# SW6106_A_A_B_C_Lighting_MCU_LED.net
KiCad netlist of a schematic drawn in Altium Designer
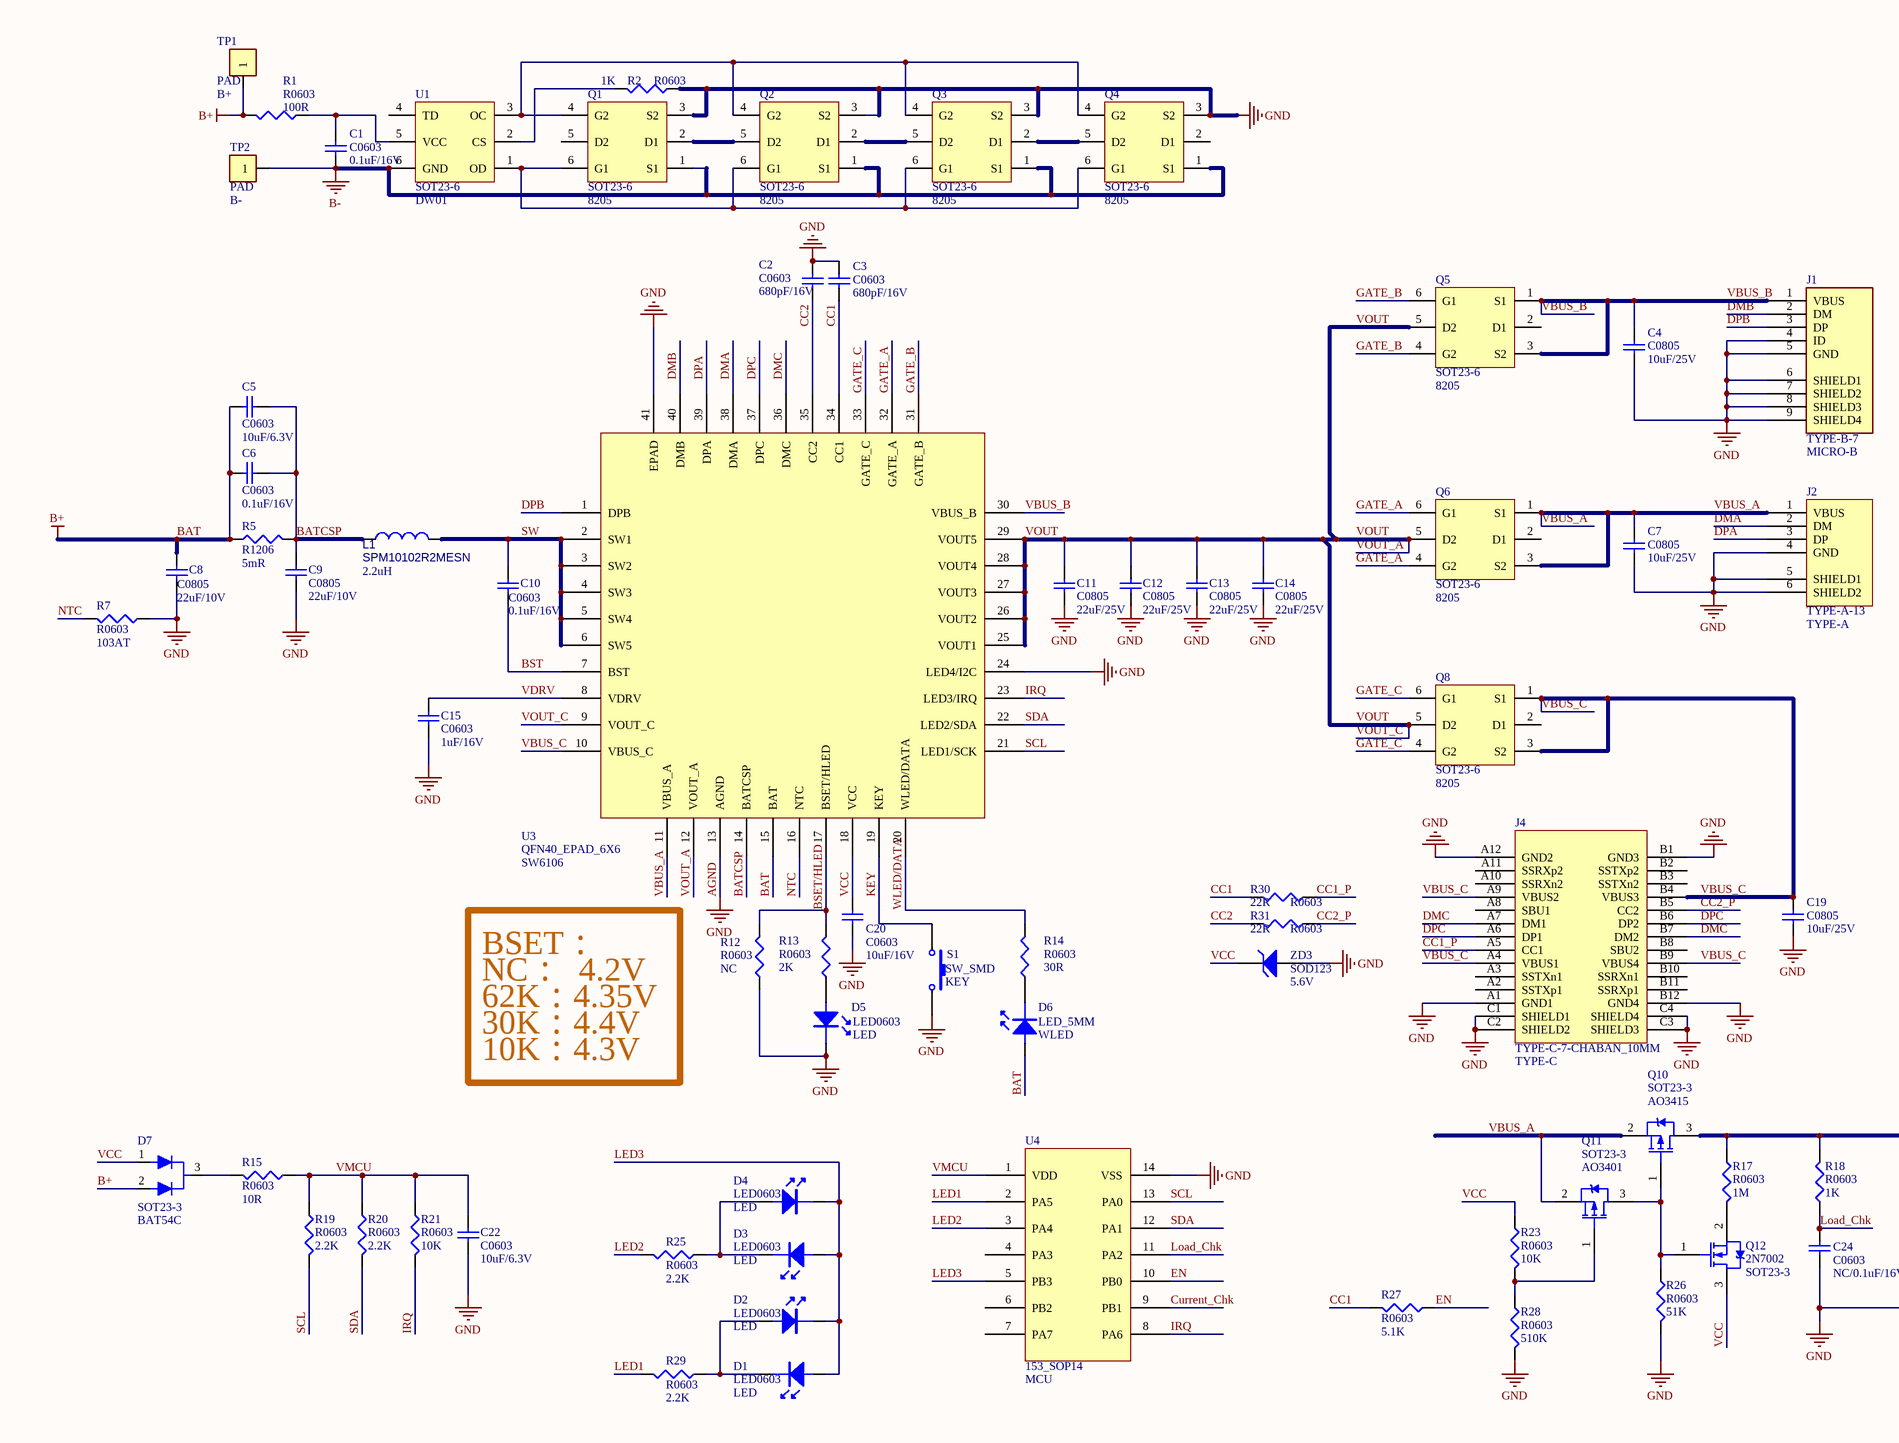
[diagram p0: SW6106+A+A+B+C+Lighting+MCU+LED.SchDoc, left]
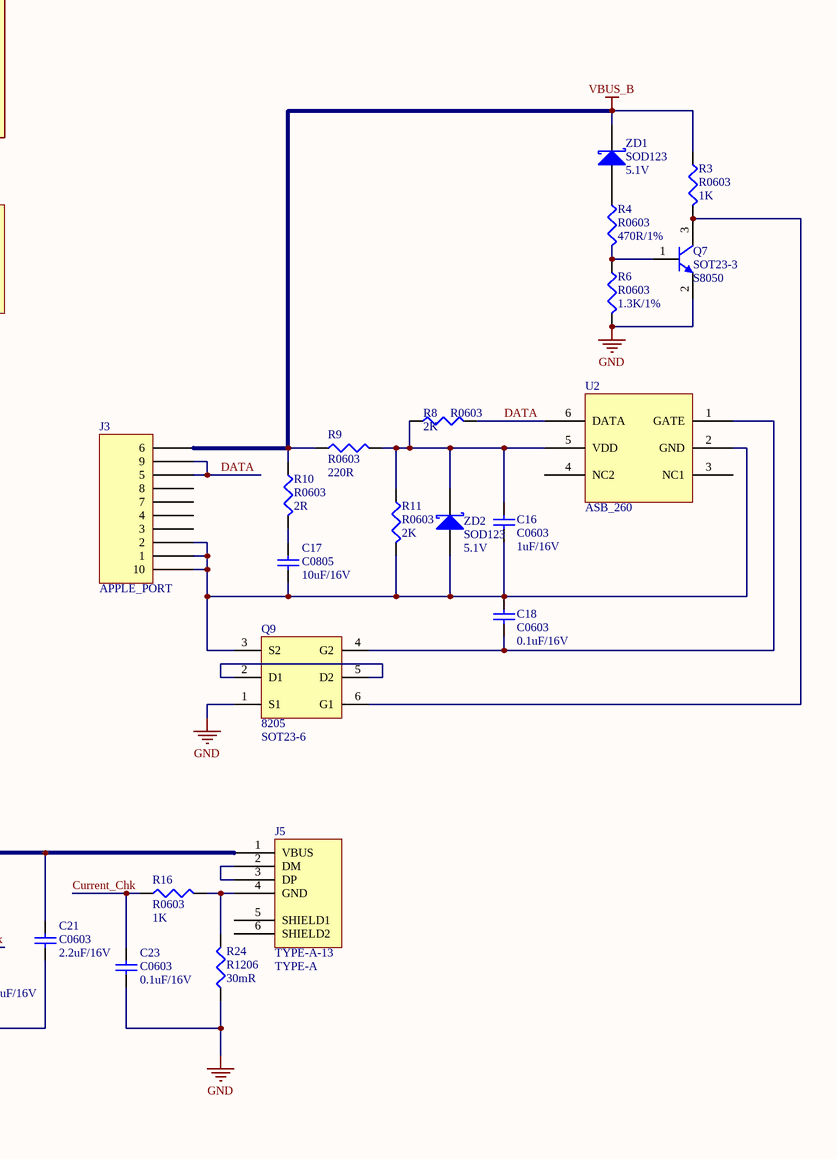
[diagram p1: SW6106+A+A+B+C+Lighting+MCU+LED.SchDoc, right]

(export (version "E")
  (design (tool "Eeschema 10.0.6"))
  (components
    (comp (ref "C1")
      (value "C0603")
      (footprint "C0603")
      (description "Capacitor")
      (fields (field (name "ALTIUM_VALUE") "0.1uF/16V") (field (name "PUBLISHER") "Altium Limited"))
      (libsource (lib "*") (part "Cap"))
    )
    (comp (ref "C2")
      (value "C0603")
      (footprint "C0603")
      (description "Capacitor")
      (fields (field (name "ALTIUM_VALUE") "680pF/16V") (field (name "PUBLISHER") "Altium Limited"))
      (libsource (lib "*") (part "CAP0603"))
    )
    (comp (ref "C3")
      (value "C0603")
      (footprint "C0603")
      (description "Capacitor")
      (fields (field (name "ALTIUM_VALUE") "680pF/16V") (field (name "PUBLISHER") "Altium Limited"))
      (libsource (lib "*") (part "CAP0603"))
    )
    (comp (ref "C4")
      (value "C0805")
      (footprint "C0805")
      (description "Capacitor")
      (fields (field (name "ALTIUM_VALUE") "10uF/25V") (field (name "PUBLISHER") "Altium Limited"))
      (libsource (lib "*") (part "CAP0603"))
    )
    (comp (ref "C5")
      (value "C0603")
      (footprint "C0603")
      (description "Capacitor")
      (fields (field (name "ALTIUM_VALUE") "10uF/6.3V") (field (name "PUBLISHER") "Altium Limited"))
      (libsource (lib "*") (part "CAP0603"))
    )
    (comp (ref "C6")
      (value "C0603")
      (footprint "C0603")
      (description "Capacitor")
      (fields (field (name "ALTIUM_VALUE") "0.1uF/16V") (field (name "PUBLISHER") "Altium Limited"))
      (libsource (lib "*") (part "CAP0603"))
    )
    (comp (ref "C7")
      (value "C0805")
      (footprint "C0805")
      (description "Capacitor")
      (fields (field (name "ALTIUM_VALUE") "10uF/25V") (field (name "PUBLISHER") "Altium Limited"))
      (libsource (lib "*") (part "CAP0603"))
    )
    (comp (ref "C8")
      (value "C0805")
      (footprint "C0805")
      (description "Capacitor")
      (fields (field (name "ALTIUM_VALUE") "22uF/10V") (field (name "PUBLISHER") "Altium Limited"))
      (libsource (lib "*") (part "CAP0805"))
    )
    (comp (ref "C9")
      (value "C0805")
      (footprint "C0805")
      (description "Capacitor")
      (fields (field (name "ALTIUM_VALUE") "22uF/10V") (field (name "PUBLISHER") "Altium Limited"))
      (libsource (lib "*") (part "CAP0805"))
    )
    (comp (ref "C10")
      (value "C0603")
      (footprint "C0603")
      (description "Capacitor")
      (fields (field (name "ALTIUM_VALUE") "0.1uF/16V") (field (name "PUBLISHER") "Altium Limited"))
      (libsource (lib "*") (part "CAP0603"))
    )
    (comp (ref "C11")
      (value "C0805")
      (footprint "C0805")
      (description "Capacitor")
      (fields (field (name "ALTIUM_VALUE") "22uF/25V") (field (name "PUBLISHER") "Altium Limited"))
      (libsource (lib "*") (part "CAP0805"))
    )
    (comp (ref "C12")
      (value "C0805")
      (footprint "C0805")
      (description "Capacitor")
      (fields (field (name "ALTIUM_VALUE") "22uF/25V") (field (name "PUBLISHER") "Altium Limited"))
      (libsource (lib "*") (part "CAP0805"))
    )
    (comp (ref "C13")
      (value "C0805")
      (footprint "C0805")
      (description "Capacitor")
      (fields (field (name "ALTIUM_VALUE") "22uF/25V") (field (name "PUBLISHER") "Altium Limited"))
      (libsource (lib "*") (part "CAP0805"))
    )
    (comp (ref "C14")
      (value "C0805")
      (footprint "C0805")
      (description "Capacitor")
      (fields (field (name "ALTIUM_VALUE") "22uF/25V") (field (name "PUBLISHER") "Altium Limited"))
      (libsource (lib "*") (part "CAP0805"))
    )
    (comp (ref "C15")
      (value "C0603")
      (footprint "C0603")
      (description "Capacitor")
      (fields (field (name "ALTIUM_VALUE") "1uF/16V") (field (name "PUBLISHER") "Altium Limited"))
      (libsource (lib "*") (part "CAP0603"))
    )
    (comp (ref "C16")
      (value "C0603")
      (footprint "C0603")
      (description "Capacitor")
      (fields (field (name "ALTIUM_VALUE") "1uF/16V") (field (name "PUBLISHER") "Altium Limited"))
      (libsource (lib "*") (part "CAP0805"))
    )
    (comp (ref "C17")
      (value "C0805")
      (footprint "C0805")
      (description "Capacitor")
      (fields (field (name "ALTIUM_VALUE") "10uF/16V") (field (name "PUBLISHER") "Altium Limited"))
      (libsource (lib "*") (part "CAP0805"))
    )
    (comp (ref "C18")
      (value "C0603")
      (footprint "C0603")
      (description "Capacitor")
      (fields (field (name "ALTIUM_VALUE") "0.1uF/16V") (field (name "PUBLISHER") "Altium Limited"))
      (libsource (lib "*") (part "CAP0805"))
    )
    (comp (ref "C19")
      (value "C0805")
      (footprint "C0805")
      (description "Capacitor")
      (fields (field (name "ALTIUM_VALUE") "10uF/25V") (field (name "PUBLISHER") "Altium Limited"))
      (libsource (lib "*") (part "CAP0603"))
    )
    (comp (ref "C20")
      (value "C0603")
      (footprint "C0603")
      (description "Capacitor")
      (fields (field (name "ALTIUM_VALUE") "10uF/16V") (field (name "PUBLISHER") "Altium Limited"))
      (libsource (lib "*") (part "CAP0603"))
    )
    (comp (ref "C21")
      (value "C0603")
      (footprint "C0603")
      (description "Capacitor")
      (fields (field (name "ALTIUM_VALUE") "2.2uF/16V") (field (name "PUBLISHER") "Altium Limited"))
      (libsource (lib "*") (part "CAP0603"))
    )
    (comp (ref "C22")
      (value "C0603")
      (footprint "C0603")
      (description "Capacitor")
      (fields (field (name "ALTIUM_VALUE") "10uF/6.3V") (field (name "PUBLISHER") "Altium Limited"))
      (libsource (lib "*") (part "CAP0603"))
    )
    (comp (ref "C23")
      (value "C0603")
      (footprint "C0603")
      (description "Capacitor")
      (fields (field (name "ALTIUM_VALUE") "0.1uF/16V") (field (name "PUBLISHER") "Altium Limited"))
      (libsource (lib "*") (part "CAP0603"))
    )
    (comp (ref "C24")
      (value "C0603")
      (footprint "C0603")
      (description "Capacitor")
      (fields (field (name "ALTIUM_VALUE") "NC/0.1uF/16V") (field (name "PUBLISHER") "Altium Limited"))
      (libsource (lib "*") (part "CAP0603"))
    )
    (comp (ref "D1") (value "LED") (footprint "LED0603") (libsource (lib "*") (part "LED")))
    (comp (ref "D2") (value "LED") (footprint "LED0603") (libsource (lib "*") (part "LED")))
    (comp (ref "D3") (value "LED") (footprint "LED0603") (libsource (lib "*") (part "LED")))
    (comp (ref "D4") (value "LED") (footprint "LED0603") (libsource (lib "*") (part "LED")))
    (comp (ref "D5") (value "LED") (footprint "LED0603") (libsource (lib "*") (part "LED")))
    (comp (ref "D6")
      (value "WLED")
      (footprint "LED_5MM")
      (fields (field (name "FOOTPRINF") "LED_5MM") (field (name "Comment") "LED_5MM"))
      (libsource (lib "*") (part "LED"))
    )
    (comp (ref "D7") (value "BAT54C") (footprint "SOT23-3") (libsource (lib "Schlib1-2012") (part "D3")))
    (comp (ref "J1")
      (value "MICRO-B")
      (footprint "TYPE-B-7")
      (fields (field (name "FOOTPRINTF") "TYPE-B-7") (field (name "Comment") "USB_MICRO_B"))
      (libsource (lib "*") (part "USB_MICRO_B"))
    )
    (comp (ref "J2")
      (value "TYPE-A")
      (footprint "TYPE-A-13")
      (fields (field (name "FOOTPRINF") "TYPE-A-13") (field (name "Comment") "TYPE-A-1"))
      (libsource (lib "*") (part "TYPE-A-1"))
    )
    (comp (ref "J3") (value "APPLE_PORT") (libsource (lib "TEST") (part "APPLE_PORT")))
    (comp (ref "J4")
      (value "TYPE-C")
      (footprint "TYPE-C-7-CHABAN_10MM")
      (libsource (lib "*") (part "TYPE-C"))
    )
    (comp (ref "J5")
      (value "TYPE-A")
      (footprint "PIE10-USB")
      (fields (field (name "FOOTPRINF") "TYPE-A-13") (field (name "Comment") "TYPE-A-1"))
      (libsource (lib "*") (part "TYPE-A-1"))
    )
    (comp (ref "L1")
      (value "SPM10102R2MESN")
      (footprint "INDUCTOR_SPM1010")
      (fields (field (name "ALTIUM_VALUE") "2.2uH"))
      (libsource (lib "*") (part "INDUCTOR"))
    )
    (comp (ref "Q1")
      (value "8205")
      (footprint "SOT23-6")
      (fields (field (name "FOOTPRINF") "SOT23-6"))
      (libsource (lib "*") (part "8205B"))
    )
    (comp (ref "Q2")
      (value "8205")
      (footprint "SOT23-6")
      (fields (field (name "FOOTPRINF") "SOT23-6"))
      (libsource (lib "*") (part "8205B"))
    )
    (comp (ref "Q3")
      (value "8205")
      (footprint "SOT23-6")
      (fields (field (name "FOOTPRINF") "SOT23-6"))
      (libsource (lib "*") (part "8205B"))
    )
    (comp (ref "Q4")
      (value "8205")
      (footprint "SOT23-6")
      (fields (field (name "FOOTPRINF") "SOT23-6"))
      (libsource (lib "*") (part "8205B"))
    )
    (comp (ref "Q5")
      (value "8205")
      (footprint "SOT23-6")
      (fields (field (name "FOOTPRINF") "SOT23-6"))
      (libsource (lib "") (part "8205B_1"))
    )
    (comp (ref "Q6")
      (value "8205")
      (footprint "SOT23-6")
      (fields (field (name "FOOTPRINF") "SOT23-6"))
      (libsource (lib "") (part "8205B_1"))
    )
    (comp (ref "Q7")
      (value "S8050")
      (footprint "SOT23-3")
      (description "NPN General Purpose Amplifier")
      (fields (field (name "PUBLISHER") "Altium Limited"))
      (libsource (lib "Miscellaneous Devices") (part "2N3904"))
    )
    (comp (ref "Q8")
      (value "8205")
      (footprint "SOT23-6")
      (fields (field (name "FOOTPRINF") "SOT23-6"))
      (libsource (lib "") (part "8205B_1"))
    )
    (comp (ref "Q9")
      (value "8205")
      (footprint "SOT23-6")
      (fields (field (name "FOOTPRINF") "SOT23-6"))
      (libsource (lib "") (part "8205B_2"))
    )
    (comp (ref "Q10")
      (value "AO3415")
      (footprint "SOT23-3")
      (description "P-Channel Power MOSFET")
      (fields (field (name "Comment") "PMOS-2") (field (name "PUBLISHER") "Altium Limited"))
      (libsource (lib "Miscellaneous Devices") (part "PMOS-2"))
    )
    (comp (ref "Q11")
      (value "AO3401")
      (footprint "SOT23-3")
      (description "P-Channel Power MOSFET")
      (fields (field (name "Comment") "PMOS-2") (field (name "PUBLISHER") "Altium Limited"))
      (libsource (lib "Miscellaneous Devices") (part "PMOS-2"))
    )
    (comp (ref "Q12")
      (value "2N7002")
      (footprint "SOT23-3")
      (description "N-Channel Power MOSFET")
      (fields (field (name "Comment") "NMOS-2") (field (name "PUBLISHER") "Altium Limited"))
      (libsource (lib "Miscellaneous Devices") (part "NMOS-2"))
    )
    (comp (ref "R1")
      (value "R0603")
      (footprint "R0603")
      (description "Resistor")
      (fields (field (name "ALTIUM_VALUE") "100R") (field (name "PUBLISHER") "Altium Limited"))
      (libsource (lib "*") (part "Res3"))
    )
    (comp (ref "R2")
      (value "R0603")
      (footprint "R0603")
      (description "Resistor")
      (fields (field (name "ALTIUM_VALUE") "1K") (field (name "PUBLISHER") "Altium Limited"))
      (libsource (lib "*") (part "Res3"))
    )
    (comp (ref "R3")
      (value "R0603")
      (footprint "R0603")
      (description "Resistor")
      (fields (field (name "ALTIUM_VALUE") "1K") (field (name "PUBLISHER") "Altium Limited"))
      (libsource (lib "Miscellaneous Devices") (part "Res3"))
    )
    (comp (ref "R4")
      (value "R0603")
      (footprint "R0603")
      (description "Resistor")
      (fields (field (name "ALTIUM_VALUE") "470R/1%") (field (name "PUBLISHER") "Altium Limited"))
      (libsource (lib "Miscellaneous Devices") (part "Res3"))
    )
    (comp (ref "R5")
      (value "R1206")
      (footprint "R1206")
      (description "Resistor")
      (fields (field (name "ALTIUM_VALUE") "5mR") (field (name "PUBLISHER") "Altium Limited"))
      (libsource (lib "*") (part "RES"))
    )
    (comp (ref "R6")
      (value "R0603")
      (footprint "R0603")
      (description "Resistor")
      (fields (field (name "ALTIUM_VALUE") "1.3K/1%") (field (name "PUBLISHER") "Altium Limited"))
      (libsource (lib "Miscellaneous Devices") (part "Res3"))
    )
    (comp (ref "R7")
      (value "R0603")
      (footprint "R0603")
      (description "Resistor")
      (fields (field (name "ALTIUM_VALUE") "103AT") (field (name "PUBLISHER") "Altium Limited"))
      (libsource (lib "*") (part "RES"))
    )
    (comp (ref "R8")
      (value "R0603")
      (footprint "R0603")
      (description "Resistor")
      (fields (field (name "ALTIUM_VALUE") "2K") (field (name "PUBLISHER") "Altium Limited"))
      (libsource (lib "Miscellaneous Devices") (part "Res3"))
    )
    (comp (ref "R9")
      (value "R0603")
      (footprint "R0603")
      (description "Resistor")
      (fields (field (name "ALTIUM_VALUE") "220R") (field (name "PUBLISHER") "Altium Limited"))
      (libsource (lib "Miscellaneous Devices") (part "Res3"))
    )
    (comp (ref "R10")
      (value "R0603")
      (footprint "R0603")
      (description "Resistor")
      (fields (field (name "ALTIUM_VALUE") "2R") (field (name "PUBLISHER") "Altium Limited"))
      (libsource (lib "Miscellaneous Devices") (part "Res3"))
    )
    (comp (ref "R11")
      (value "R0603")
      (footprint "R0603")
      (description "Resistor")
      (fields (field (name "ALTIUM_VALUE") "2K") (field (name "PUBLISHER") "Altium Limited"))
      (libsource (lib "Miscellaneous Devices") (part "Res3"))
    )
    (comp (ref "R12")
      (value "R0603")
      (footprint "R0603")
      (description "Resistor")
      (fields (field (name "ALTIUM_VALUE") "NC") (field (name "PUBLISHER") "Altium Limited"))
      (libsource (lib "*") (part "RES"))
    )
    (comp (ref "R13")
      (value "R0603")
      (footprint "R0603")
      (description "Resistor")
      (fields (field (name "ALTIUM_VALUE") "2K") (field (name "PUBLISHER") "Altium Limited"))
      (libsource (lib "*") (part "RES"))
    )
    (comp (ref "R14")
      (value "R0603")
      (footprint "R0603")
      (description "Resistor")
      (fields (field (name "ALTIUM_VALUE") "30R") (field (name "PUBLISHER") "Altium Limited"))
      (libsource (lib "*") (part "RES"))
    )
    (comp (ref "R15")
      (value "R0603")
      (footprint "R0603")
      (description "Resistor")
      (fields (field (name "ALTIUM_VALUE") "10R") (field (name "PUBLISHER") "Altium Limited"))
      (libsource (lib "*") (part "RES"))
    )
    (comp (ref "R16")
      (value "R0603")
      (footprint "R0603")
      (description "Resistor")
      (fields (field (name "ALTIUM_VALUE") "1K") (field (name "PUBLISHER") "Altium Limited"))
      (libsource (lib "*") (part "RES"))
    )
    (comp (ref "R17")
      (value "R0603")
      (footprint "R0603")
      (description "Resistor")
      (fields (field (name "ALTIUM_VALUE") "1M") (field (name "PUBLISHER") "Altium Limited"))
      (libsource (lib "*") (part "RES"))
    )
    (comp (ref "R18")
      (value "R0603")
      (footprint "R0603")
      (description "Resistor")
      (fields (field (name "ALTIUM_VALUE") "1K") (field (name "PUBLISHER") "Altium Limited"))
      (libsource (lib "*") (part "RES"))
    )
    (comp (ref "R19")
      (value "R0603")
      (footprint "R0603")
      (description "Resistor")
      (fields (field (name "ALTIUM_VALUE") "2.2K") (field (name "PUBLISHER") "Altium Limited"))
      (libsource (lib "*") (part "RES"))
    )
    (comp (ref "R20")
      (value "R0603")
      (footprint "R0603")
      (description "Resistor")
      (fields (field (name "ALTIUM_VALUE") "2.2K") (field (name "PUBLISHER") "Altium Limited"))
      (libsource (lib "*") (part "RES"))
    )
    (comp (ref "R21")
      (value "R0603")
      (footprint "R0603")
      (description "Resistor")
      (fields (field (name "ALTIUM_VALUE") "10K") (field (name "PUBLISHER") "Altium Limited"))
      (libsource (lib "*") (part "RES"))
    )
    (comp (ref "R23")
      (value "R0603")
      (footprint "R0603")
      (description "Resistor")
      (fields (field (name "ALTIUM_VALUE") "10K") (field (name "PUBLISHER") "Altium Limited"))
      (libsource (lib "*") (part "RES"))
    )
    (comp (ref "R24")
      (value "R1206")
      (footprint "C-1206A")
      (description "Resistor")
      (fields (field (name "ALTIUM_VALUE") "30mR") (field (name "PUBLISHER") "Altium Limited"))
      (libsource (lib "*") (part "RES"))
    )
    (comp (ref "R25")
      (value "R0603")
      (footprint "R0603")
      (description "Resistor")
      (fields (field (name "ALTIUM_VALUE") "2.2K") (field (name "PUBLISHER") "Altium Limited"))
      (libsource (lib "*") (part "RES"))
    )
    (comp (ref "R26")
      (value "R0603")
      (footprint "R0603")
      (description "Resistor")
      (fields (field (name "ALTIUM_VALUE") "51K") (field (name "PUBLISHER") "Altium Limited"))
      (libsource (lib "*") (part "RES"))
    )
    (comp (ref "R27")
      (value "R0603")
      (footprint "R0603")
      (description "Resistor")
      (fields (field (name "ALTIUM_VALUE") "5.1K") (field (name "PUBLISHER") "Altium Limited"))
      (libsource (lib "*") (part "RES"))
    )
    (comp (ref "R28")
      (value "R0603")
      (footprint "R0603")
      (description "Resistor")
      (fields (field (name "ALTIUM_VALUE") "510K") (field (name "PUBLISHER") "Altium Limited"))
      (libsource (lib "*") (part "RES"))
    )
    (comp (ref "R29")
      (value "R0603")
      (footprint "R0603")
      (description "Resistor")
      (fields (field (name "ALTIUM_VALUE") "2.2K") (field (name "PUBLISHER") "Altium Limited"))
      (libsource (lib "*") (part "RES"))
    )
    (comp (ref "R30")
      (value "R0603")
      (footprint "R0603")
      (description "Resistor")
      (fields (field (name "ALTIUM_VALUE") "22R") (field (name "PUBLISHER") "Altium Limited"))
      (libsource (lib "*") (part "RES"))
    )
    (comp (ref "R31")
      (value "R0603")
      (footprint "R0603")
      (description "Resistor")
      (fields (field (name "ALTIUM_VALUE") "22R") (field (name "PUBLISHER") "Altium Limited"))
      (libsource (lib "*") (part "RES"))
    )
    (comp (ref "S1")
      (value "KEY")
      (footprint "SW_SMD")
      (fields (field (name "FOOTPRINF") "SW_SMD"))
      (libsource (lib "*") (part "SW K"))
    )
    (comp (ref "TP1") (value "B+") (footprint "PAD") (libsource (lib "*") (part "Test Point")))
    (comp (ref "TP2") (value "B-") (footprint "PAD") (libsource (lib "") (part "Test Point_1")))
    (comp (ref "U1")
      (value "DW01")
      (footprint "SOT23-6")
      (fields (field (name "FOOTPRINF") "SOT23-6"))
      (libsource (lib "*") (part "DW01"))
    )
    (comp (ref "U2") (value "ASB_260") (footprint "SOT-23-") (libsource (lib "TEST") (part "ASB_260")))
    (comp (ref "U3")
      (value "SW6106")
      (footprint "QFN40_EPAD_6X6")
      (libsource (lib "TEST") (part "SW6106_AFC"))
    )
    (comp (ref "U4")
      (value "153_SOP14")
      (fields (field (name "ALTIUM_VALUE") "MCU"))
      (libsource (lib "TEST") (part "153_SOP14"))
    )
    (comp (ref "ZD1")
      (value "5.1V")
      (footprint "SOD123")
      (description "Schottky Rectifier")
      (fields (field (name "Comment") "SOD123") (field (name "PUBLISHER") "Altium Limited"))
      (libsource (lib "Miscellaneous Devices") (part "Diode 11DQ03"))
    )
    (comp (ref "ZD2")
      (value "5.1V")
      (footprint "SOD123")
      (description "Schottky Rectifier")
      (fields (field (name "Comment") "SOD123") (field (name "PUBLISHER") "Altium Limited"))
      (libsource (lib "Miscellaneous Devices") (part "Diode 11DQ03"))
    )
    (comp (ref "ZD3")
      (value "SOD123")
      (footprint "SOD-123")
      (description "Zener Diode")
      (fields (field (name "ALTIUM_VALUE") "5.6V"))
      (libsource (lib "Miscellaneous Devices") (part "D Zener"))
    )
  )
  (nets
    (net (code "1") (name "/BATCSP") (class "Default")
      (node (ref "C5") (pin "2") (pinfunction "2_2") (pintype "passive"))
      (node (ref "C6") (pin "2") (pinfunction "2_2") (pintype "passive"))
      (node (ref "C9") (pin "2") (pinfunction "2_2") (pintype "passive"))
      (node (ref "L1") (pin "1") (pinfunction "1_1") (pintype "passive"))
      (node (ref "R5") (pin "2") (pinfunction "2_2") (pintype "passive"))
      (node (ref "U3") (pin "14") (pinfunction "BATCSP_14") (pintype "passive"))
    )
    (net (code "2") (name "/BSET{slash}HLED") (class "Default")
      (node (ref "R12") (pin "2") (pinfunction "2_2") (pintype "passive"))
      (node (ref "R13") (pin "2") (pinfunction "2_2") (pintype "passive"))
      (node (ref "U3") (pin "17") (pinfunction "BSET/HLED_17") (pintype "passive"))
    )
    (net (code "3") (name "/BST") (class "Default")
      (node (ref "C10") (pin "1") (pinfunction "1_1") (pintype "passive"))
      (node (ref "U3") (pin "7") (pinfunction "BST_7") (pintype "passive"))
    )
    (net (code "4") (name "/CC1") (class "Default")
      (node (ref "C3") (pin "1") (pinfunction "1_1") (pintype "passive"))
      (node (ref "R27") (pin "2") (pinfunction "2_2") (pintype "passive"))
      (node (ref "R30") (pin "2") (pinfunction "2_2") (pintype "passive"))
      (node (ref "U3") (pin "34") (pinfunction "CC1_34") (pintype "passive"))
    )
    (net (code "5") (name "/CC1_P") (class "Default")
      (node (ref "J4") (pin "A5") (pinfunction "CC1_A5") (pintype "passive"))
      (node (ref "R30") (pin "1") (pinfunction "1_1") (pintype "passive"))
    )
    (net (code "6") (name "/CC2") (class "Default")
      (node (ref "C2") (pin "1") (pinfunction "1_1") (pintype "passive"))
      (node (ref "R31") (pin "2") (pinfunction "2_2") (pintype "passive"))
      (node (ref "U3") (pin "35") (pinfunction "CC2_35") (pintype "passive"))
    )
    (net (code "7") (name "/CC2_P") (class "Default")
      (node (ref "J4") (pin "B5") (pinfunction "CC2_B5") (pintype "passive"))
      (node (ref "R31") (pin "1") (pinfunction "1_1") (pintype "passive"))
    )
    (net (code "8") (name "/Current_Chk") (class "Default")
      (node (ref "C23") (pin "2") (pinfunction "2_2") (pintype "passive"))
      (node (ref "R16") (pin "1") (pinfunction "1_1") (pintype "passive"))
      (node (ref "U4") (pin "9") (pinfunction "PB1_9") (pintype "passive"))
    )
    (net (code "9") (name "/DATA") (class "Default")
      (node (ref "J3") (pin "5") (pinfunction "5_5") (pintype "passive"))
      (node (ref "J3") (pin "9") (pinfunction "9_9") (pintype "passive"))
      (node (ref "R8") (pin "2") (pinfunction "2_2") (pintype "passive"))
      (node (ref "U2") (pin "6") (pinfunction "DATA_6") (pintype "passive"))
    )
    (net (code "10") (name "/DMA") (class "Default")
      (node (ref "J2") (pin "2") (pinfunction "DM_2") (pintype "passive"))
      (node (ref "U3") (pin "38") (pinfunction "DMA_38") (pintype "passive"))
    )
    (net (code "11") (name "/DMB") (class "Default")
      (node (ref "J1") (pin "2") (pinfunction "DM_2") (pintype "passive"))
      (node (ref "U3") (pin "40") (pinfunction "DMB_40") (pintype "passive"))
    )
    (net (code "12") (name "/DMC") (class "Default")
      (node (ref "J4") (pin "A7") (pinfunction "DM1_A7") (pintype "passive"))
      (node (ref "J4") (pin "B7") (pinfunction "DM2_B7") (pintype "passive"))
      (node (ref "U3") (pin "36") (pinfunction "DMC_36") (pintype "passive"))
    )
    (net (code "13") (name "/DPA") (class "Default")
      (node (ref "J2") (pin "3") (pinfunction "DP_3") (pintype "passive"))
      (node (ref "U3") (pin "39") (pinfunction "DPA_39") (pintype "passive"))
    )
    (net (code "14") (name "/DPB") (class "Default")
      (node (ref "J1") (pin "3") (pinfunction "DP_3") (pintype "passive"))
      (node (ref "U3") (pin "1") (pinfunction "DPB_1") (pintype "passive"))
    )
    (net (code "15") (name "/DPC") (class "Default")
      (node (ref "J4") (pin "A6") (pinfunction "DP1_A6") (pintype "passive"))
      (node (ref "J4") (pin "B6") (pinfunction "DP2_B6") (pintype "passive"))
      (node (ref "U3") (pin "37") (pinfunction "DPC_37") (pintype "passive"))
    )
    (net (code "16") (name "/EN") (class "Default")
      (node (ref "R27") (pin "1") (pinfunction "1_1") (pintype "passive"))
      (node (ref "U4") (pin "10") (pinfunction "PB0_10") (pintype "passive"))
    )
    (net (code "17") (name "/GATE_A") (class "Default")
      (node (ref "Q6") (pin "4") (pinfunction "G2_4") (pintype "passive"))
      (node (ref "Q6") (pin "6") (pinfunction "G1_6") (pintype "passive"))
      (node (ref "U3") (pin "32") (pinfunction "GATE_A_32") (pintype "passive"))
    )
    (net (code "18") (name "/GATE_B") (class "Default")
      (node (ref "Q5") (pin "4") (pinfunction "G2_4") (pintype "passive"))
      (node (ref "Q5") (pin "6") (pinfunction "G1_6") (pintype "passive"))
      (node (ref "U3") (pin "31") (pinfunction "GATE_B_31") (pintype "passive"))
    )
    (net (code "19") (name "/GATE_C") (class "Default")
      (node (ref "Q8") (pin "4") (pinfunction "G2_4") (pintype "passive"))
      (node (ref "Q8") (pin "6") (pinfunction "G1_6") (pintype "passive"))
      (node (ref "U3") (pin "33") (pinfunction "GATE_C_33") (pintype "passive"))
    )
    (net (code "20") (name "/IRQ") (class "Default")
      (node (ref "R21") (pin "2") (pinfunction "2_2") (pintype "passive"))
      (node (ref "U3") (pin "23") (pinfunction "LED3/IRQ_23") (pintype "passive"))
      (node (ref "U4") (pin "8") (pinfunction "PA6_8") (pintype "passive"))
    )
    (net (code "21") (name "/KEY") (class "Default")
      (node (ref "S1") (pin "1") (pinfunction "1_1") (pintype "passive"))
      (node (ref "U3") (pin "19") (pinfunction "KEY_19") (pintype "passive"))
    )
    (net (code "22") (name "/LED1") (class "Default")
      (node (ref "R29") (pin "2") (pinfunction "2_2") (pintype "passive"))
      (node (ref "U4") (pin "2") (pinfunction "PA5_2") (pintype "passive"))
    )
    (net (code "23") (name "/LED2") (class "Default")
      (node (ref "R25") (pin "2") (pinfunction "2_2") (pintype "passive"))
      (node (ref "U4") (pin "3") (pinfunction "PA4_3") (pintype "passive"))
    )
    (net (code "24") (name "/LED3") (class "Default")
      (node (ref "D1") (pin "1") (pinfunction "A_1") (pintype "passive"))
      (node (ref "D2") (pin "2") (pinfunction "K_2") (pintype "passive"))
      (node (ref "D3") (pin "1") (pinfunction "A_1") (pintype "passive"))
      (node (ref "D4") (pin "2") (pinfunction "K_2") (pintype "passive"))
      (node (ref "U4") (pin "5") (pinfunction "PB3_5") (pintype "passive"))
    )
    (net (code "25") (name "/Load_Chk") (class "Default")
      (node (ref "C24") (pin "2") (pinfunction "2_2") (pintype "passive"))
      (node (ref "R18") (pin "1") (pinfunction "1_1") (pintype "passive"))
      (node (ref "U4") (pin "11") (pinfunction "PA2_11") (pintype "passive"))
    )
    (net (code "26") (name "/NTC") (class "Default")
      (node (ref "R7") (pin "2") (pinfunction "2_2") (pintype "passive"))
      (node (ref "U3") (pin "16") (pinfunction "NTC_16") (pintype "passive"))
    )
    (net (code "27") (name "/SCL") (class "Default")
      (node (ref "R19") (pin "2") (pinfunction "2_2") (pintype "passive"))
      (node (ref "U3") (pin "21") (pinfunction "LED1/SCK_21") (pintype "passive"))
      (node (ref "U4") (pin "13") (pinfunction "PA0_13") (pintype "passive"))
    )
    (net (code "28") (name "/SDA") (class "Default")
      (node (ref "R20") (pin "2") (pinfunction "2_2") (pintype "passive"))
      (node (ref "U3") (pin "22") (pinfunction "LED2/SDA_22") (pintype "passive"))
      (node (ref "U4") (pin "12") (pinfunction "PA1_12") (pintype "passive"))
    )
    (net (code "29") (name "/SW") (class "Default")
      (node (ref "C10") (pin "2") (pinfunction "2_2") (pintype "passive"))
      (node (ref "L1") (pin "2") (pinfunction "2_2") (pintype "passive"))
      (node (ref "U3") (pin "2") (pinfunction "SW1_2") (pintype "passive"))
      (node (ref "U3") (pin "3") (pinfunction "SW2_3") (pintype "passive"))
      (node (ref "U3") (pin "4") (pinfunction "SW3_4") (pintype "passive"))
      (node (ref "U3") (pin "5") (pinfunction "SW4_5") (pintype "passive"))
      (node (ref "U3") (pin "6") (pinfunction "SW5_6") (pintype "passive"))
    )
    (net (code "30") (name "/VBUS_A") (class "Default")
      (node (ref "C7") (pin "2") (pinfunction "2_2") (pintype "passive"))
      (node (ref "J2") (pin "1") (pinfunction "VBUS_1") (pintype "passive"))
      (node (ref "Q10") (pin "2") (pinfunction "S_2") (pintype "passive"))
      (node (ref "Q11") (pin "2") (pinfunction "S_2") (pintype "passive"))
      (node (ref "Q6") (pin "1") (pinfunction "S1_1") (pintype "passive"))
      (node (ref "Q6") (pin "3") (pinfunction "S2_3") (pintype "passive"))
      (node (ref "U3") (pin "11") (pinfunction "VBUS_A_11") (pintype "passive"))
    )
    (net (code "31") (name "/VBUS_C") (class "Default")
      (node (ref "C19") (pin "2") (pinfunction "2_2") (pintype "passive"))
      (node (ref "J4") (pin "A4") (pinfunction "VBUS1_A4") (pintype "passive"))
      (node (ref "J4") (pin "A9") (pinfunction "VBUS2_A9") (pintype "passive"))
      (node (ref "J4") (pin "B4") (pinfunction "VBUS3_B4") (pintype "passive"))
      (node (ref "J4") (pin "B9") (pinfunction "VBUS4_B9") (pintype "passive"))
      (node (ref "Q8") (pin "1") (pinfunction "S1_1") (pintype "passive"))
      (node (ref "Q8") (pin "3") (pinfunction "S2_3") (pintype "passive"))
      (node (ref "U3") (pin "10") (pinfunction "VBUS_C_10") (pintype "passive"))
    )
    (net (code "32") (name "/VCC") (class "Default")
      (node (ref "C20") (pin "2") (pinfunction "2_2") (pintype "passive"))
      (node (ref "D7") (pin "1") (pintype "passive"))
      (node (ref "Q12") (pin "3") (pinfunction "D_3") (pintype "passive"))
      (node (ref "R23") (pin "1") (pinfunction "1_1") (pintype "passive"))
      (node (ref "U3") (pin "18") (pinfunction "VCC_18") (pintype "passive"))
      (node (ref "ZD3") (pin "2") (pinfunction "K_2") (pintype "passive"))
    )
    (net (code "33") (name "/VDRV") (class "Default")
      (node (ref "C15") (pin "2") (pinfunction "2_2") (pintype "passive"))
      (node (ref "U3") (pin "8") (pinfunction "VDRV_8") (pintype "passive"))
    )
    (net (code "34") (name "/VMCU") (class "Default")
      (node (ref "C22") (pin "1") (pinfunction "1_1") (pintype "passive"))
      (node (ref "R15") (pin "1") (pinfunction "1_1") (pintype "passive"))
      (node (ref "R19") (pin "1") (pinfunction "1_1") (pintype "passive"))
      (node (ref "R20") (pin "1") (pinfunction "1_1") (pintype "passive"))
      (node (ref "R21") (pin "1") (pinfunction "1_1") (pintype "passive"))
      (node (ref "U4") (pin "1") (pinfunction "VDD_1") (pintype "passive"))
    )
    (net (code "35") (name "/VOUT") (class "Default")
      (node (ref "C11") (pin "2") (pinfunction "2_2") (pintype "passive"))
      (node (ref "C12") (pin "2") (pinfunction "2_2") (pintype "passive"))
      (node (ref "C13") (pin "2") (pinfunction "2_2") (pintype "passive"))
      (node (ref "C14") (pin "2") (pinfunction "2_2") (pintype "passive"))
      (node (ref "Q5") (pin "5") (pinfunction "D2_5") (pintype "passive"))
      (node (ref "Q6") (pin "5") (pinfunction "D2_5") (pintype "passive"))
      (node (ref "Q8") (pin "5") (pinfunction "D2_5") (pintype "passive"))
      (node (ref "U3") (pin "12") (pinfunction "VOUT_A_12") (pintype "passive"))
      (node (ref "U3") (pin "25") (pinfunction "VOUT1_25") (pintype "passive"))
      (node (ref "U3") (pin "26") (pinfunction "VOUT2_26") (pintype "passive"))
      (node (ref "U3") (pin "27") (pinfunction "VOUT3_27") (pintype "passive"))
      (node (ref "U3") (pin "28") (pinfunction "VOUT4_28") (pintype "passive"))
      (node (ref "U3") (pin "29") (pinfunction "VOUT5_29") (pintype "passive"))
      (node (ref "U3") (pin "9") (pinfunction "VOUT_C_9") (pintype "passive"))
    )
    (net (code "36") (name "/WLED{slash}DATA") (class "Default")
      (node (ref "R14") (pin "2") (pinfunction "2_2") (pintype "passive"))
      (node (ref "U3") (pin "20") (pinfunction "WLED/DATA_20") (pintype "passive"))
    )
    (net (code "37") (name "B+") (class "Default")
      (node (ref "C5") (pin "1") (pinfunction "1_1") (pintype "passive"))
      (node (ref "C6") (pin "1") (pinfunction "1_1") (pintype "passive"))
      (node (ref "C8") (pin "2") (pinfunction "2_2") (pintype "passive"))
      (node (ref "D6") (pin "1") (pinfunction "A_1") (pintype "passive"))
      (node (ref "D7") (pin "2") (pintype "passive"))
      (node (ref "R1") (pin "2") (pinfunction "2_2") (pintype "passive"))
      (node (ref "R5") (pin "1") (pinfunction "1_1") (pintype "passive"))
      (node (ref "TP1") (pin "1") (pinfunction "1_1") (pintype "passive"))
      (node (ref "U3") (pin "15") (pinfunction "BAT_15") (pintype "passive"))
    )
    (net (code "38") (name "B-") (class "Default")
      (node (ref "C1") (pin "1") (pinfunction "1_1") (pintype "passive"))
      (node (ref "Q1") (pin "1") (pinfunction "S1_1") (pintype "passive"))
      (node (ref "Q2") (pin "1") (pinfunction "S1_1") (pintype "passive"))
      (node (ref "Q3") (pin "1") (pinfunction "S1_1") (pintype "passive"))
      (node (ref "Q4") (pin "1") (pinfunction "S1_1") (pintype "passive"))
      (node (ref "TP2") (pin "1") (pinfunction "1_1") (pintype "passive"))
      (node (ref "U1") (pin "6") (pinfunction "GND_6") (pintype "passive"))
    )
    (net (code "39") (name "GND") (class "Default")
      (node (ref "C11") (pin "1") (pinfunction "1_1") (pintype "passive"))
      (node (ref "C12") (pin "1") (pinfunction "1_1") (pintype "passive"))
      (node (ref "C13") (pin "1") (pinfunction "1_1") (pintype "passive"))
      (node (ref "C14") (pin "1") (pinfunction "1_1") (pintype "passive"))
      (node (ref "C15") (pin "1") (pinfunction "1_1") (pintype "passive"))
      (node (ref "C19") (pin "1") (pinfunction "1_1") (pintype "passive"))
      (node (ref "C2") (pin "2") (pinfunction "2_2") (pintype "passive"))
      (node (ref "C20") (pin "1") (pinfunction "1_1") (pintype "passive"))
      (node (ref "C21") (pin "1") (pinfunction "1_1") (pintype "passive"))
      (node (ref "C22") (pin "2") (pinfunction "2_2") (pintype "passive"))
      (node (ref "C23") (pin "1") (pinfunction "1_1") (pintype "passive"))
      (node (ref "C24") (pin "1") (pinfunction "1_1") (pintype "passive"))
      (node (ref "C3") (pin "2") (pinfunction "2_2") (pintype "passive"))
      (node (ref "C4") (pin "1") (pinfunction "1_1") (pintype "passive"))
      (node (ref "C7") (pin "1") (pinfunction "1_1") (pintype "passive"))
      (node (ref "C8") (pin "1") (pinfunction "1_1") (pintype "passive"))
      (node (ref "C9") (pin "1") (pinfunction "1_1") (pintype "passive"))
      (node (ref "D5") (pin "2") (pinfunction "K_2") (pintype "passive"))
      (node (ref "J1") (pin "4") (pinfunction "ID_4") (pintype "passive"))
      (node (ref "J1") (pin "5") (pinfunction "GND_5") (pintype "passive"))
      (node (ref "J1") (pin "6") (pinfunction "SHIELD1_6") (pintype "passive"))
      (node (ref "J1") (pin "7") (pinfunction "SHIELD2_7") (pintype "passive"))
      (node (ref "J1") (pin "8") (pinfunction "SHIELD3_8") (pintype "passive"))
      (node (ref "J1") (pin "9") (pinfunction "SHIELD4_9") (pintype "passive"))
      (node (ref "J2") (pin "4") (pinfunction "GND_4") (pintype "passive"))
      (node (ref "J2") (pin "5") (pinfunction "SHIELD1_5") (pintype "passive"))
      (node (ref "J2") (pin "6") (pinfunction "SHIELD2_6") (pintype "passive"))
      (node (ref "J4") (pin "A1") (pinfunction "GND1_A1") (pintype "passive"))
      (node (ref "J4") (pin "A12") (pinfunction "GND2_A12") (pintype "passive"))
      (node (ref "J4") (pin "B1") (pinfunction "GND3_B1") (pintype "passive"))
      (node (ref "J4") (pin "B12") (pinfunction "GND4_B12") (pintype "passive"))
      (node (ref "J4") (pin "C1") (pinfunction "SHIELD1_C1") (pintype "passive"))
      (node (ref "J4") (pin "C2") (pinfunction "SHIELD2_C2") (pintype "passive"))
      (node (ref "J4") (pin "C3") (pinfunction "SHIELD3_C3") (pintype "passive"))
      (node (ref "J4") (pin "C4") (pinfunction "SHIELD4_C4") (pintype "passive"))
      (node (ref "Q1") (pin "3") (pinfunction "S2_3") (pintype "passive"))
      (node (ref "Q2") (pin "3") (pinfunction "S2_3") (pintype "passive"))
      (node (ref "Q3") (pin "3") (pinfunction "S2_3") (pintype "passive"))
      (node (ref "Q4") (pin "3") (pinfunction "S2_3") (pintype "passive"))
      (node (ref "Q7") (pin "2") (pinfunction "E_2") (pintype "passive"))
      (node (ref "Q9") (pin "1") (pinfunction "S1_1") (pintype "passive"))
      (node (ref "R12") (pin "1") (pinfunction "1_1") (pintype "passive"))
      (node (ref "R2") (pin "1") (pinfunction "1_1") (pintype "passive"))
      (node (ref "R24") (pin "1") (pinfunction "1_1") (pintype "passive"))
      (node (ref "R26") (pin "2") (pinfunction "2_2") (pintype "passive"))
      (node (ref "R28") (pin "2") (pinfunction "2_2") (pintype "passive"))
      (node (ref "R6") (pin "2") (pinfunction "2_2") (pintype "passive"))
      (node (ref "R7") (pin "1") (pinfunction "1_1") (pintype "passive"))
      (node (ref "S1") (pin "2") (pinfunction "2_2") (pintype "passive"))
      (node (ref "U3") (pin "13") (pinfunction "AGND_13") (pintype "passive"))
      (node (ref "U3") (pin "24") (pinfunction "LED4/I2C_24") (pintype "passive"))
      (node (ref "U3") (pin "41") (pinfunction "EPAD_41") (pintype "passive"))
      (node (ref "U4") (pin "14") (pinfunction "VSS_14") (pintype "passive"))
      (node (ref "ZD3") (pin "1") (pinfunction "A_1") (pintype "passive"))
    )
    (net (code "40") (name "Net-(C17-Pad2)") (class "Default")
      (node (ref "C17") (pin "2") (pinfunction "2_2") (pintype "passive"))
      (node (ref "R10") (pin "2") (pinfunction "2_2") (pintype "passive"))
    )
    (net (code "41") (name "Net-(D1-K)") (class "Default")
      (node (ref "D1") (pin "2") (pinfunction "K_2") (pintype "passive"))
      (node (ref "D2") (pin "1") (pinfunction "A_1") (pintype "passive"))
      (node (ref "R29") (pin "1") (pinfunction "1_1") (pintype "passive"))
    )
    (net (code "42") (name "Net-(D3-K)") (class "Default")
      (node (ref "D3") (pin "2") (pinfunction "K_2") (pintype "passive"))
      (node (ref "D4") (pin "1") (pinfunction "A_1") (pintype "passive"))
      (node (ref "R25") (pin "1") (pinfunction "1_1") (pintype "passive"))
    )
    (net (code "43") (name "Net-(D5-A)") (class "Default")
      (node (ref "D5") (pin "1") (pinfunction "A_1") (pintype "passive"))
      (node (ref "R13") (pin "1") (pinfunction "1_1") (pintype "passive"))
    )
    (net (code "44") (name "Net-(D6-K)") (class "Default")
      (node (ref "D6") (pin "2") (pinfunction "K_2") (pintype "passive"))
      (node (ref "R14") (pin "1") (pinfunction "1_1") (pintype "passive"))
    )
    (net (code "45") (name "Net-(D7-Pad3)") (class "Default")
      (node (ref "D7") (pin "3") (pintype "passive"))
      (node (ref "R15") (pin "2") (pinfunction "2_2") (pintype "passive"))
    )
    (net (code "46") (name "Net-(J5-DM)") (class "Default")
      (node (ref "J5") (pin "2") (pinfunction "DM_2") (pintype "passive"))
      (node (ref "J5") (pin "3") (pinfunction "DP_3") (pintype "passive"))
    )
    (net (code "47") (name "Net-(J5-GND)") (class "Default")
      (node (ref "J5") (pin "4") (pinfunction "GND_4") (pintype "passive"))
      (node (ref "R16") (pin "2") (pinfunction "2_2") (pintype "passive"))
      (node (ref "R24") (pin "2") (pinfunction "2_2") (pintype "passive"))
    )
    (net (code "48") (name "Net-(J5-VBUS)") (class "Default")
      (node (ref "C21") (pin "2") (pinfunction "2_2") (pintype "passive"))
      (node (ref "J5") (pin "1") (pinfunction "VBUS_1") (pintype "passive"))
      (node (ref "Q10") (pin "3") (pinfunction "D_3") (pintype "passive"))
      (node (ref "R17") (pin "1") (pinfunction "1_1") (pintype "passive"))
      (node (ref "R18") (pin "2") (pinfunction "2_2") (pintype "passive"))
    )
    (net (code "49") (name "Net-(Q1-D1)") (class "Default")
      (node (ref "Q1") (pin "2") (pinfunction "D1_2") (pintype "passive"))
      (node (ref "Q2") (pin "5") (pinfunction "D2_5") (pintype "passive"))
    )
    (net (code "50") (name "Net-(Q1-G1)") (class "Default")
      (node (ref "Q1") (pin "6") (pinfunction "G1_6") (pintype "passive"))
      (node (ref "Q2") (pin "6") (pinfunction "G1_6") (pintype "passive"))
      (node (ref "Q3") (pin "6") (pinfunction "G1_6") (pintype "passive"))
      (node (ref "Q4") (pin "6") (pinfunction "G1_6") (pintype "passive"))
      (node (ref "U1") (pin "1") (pinfunction "OD_1") (pintype "passive"))
    )
    (net (code "51") (name "Net-(Q1-G2)") (class "Default")
      (node (ref "Q1") (pin "4") (pinfunction "G2_4") (pintype "passive"))
      (node (ref "Q2") (pin "4") (pinfunction "G2_4") (pintype "passive"))
      (node (ref "Q3") (pin "4") (pinfunction "G2_4") (pintype "passive"))
      (node (ref "Q4") (pin "4") (pinfunction "G2_4") (pintype "passive"))
      (node (ref "U1") (pin "3") (pinfunction "OC_3") (pintype "passive"))
    )
    (net (code "52") (name "Net-(Q2-D1)") (class "Default")
      (node (ref "Q2") (pin "2") (pinfunction "D1_2") (pintype "passive"))
      (node (ref "Q3") (pin "5") (pinfunction "D2_5") (pintype "passive"))
    )
    (net (code "53") (name "Net-(Q3-D1)") (class "Default")
      (node (ref "Q3") (pin "2") (pinfunction "D1_2") (pintype "passive"))
      (node (ref "Q4") (pin "5") (pinfunction "D2_5") (pintype "passive"))
    )
    (net (code "54") (name "Net-(Q7-B)") (class "Default")
      (node (ref "Q7") (pin "1") (pinfunction "B_1") (pintype "passive"))
      (node (ref "R4") (pin "2") (pinfunction "2_2") (pintype "passive"))
      (node (ref "R6") (pin "1") (pinfunction "1_1") (pintype "passive"))
    )
    (net (code "55") (name "Net-(Q7-C)") (class "Default")
      (node (ref "Q7") (pin "3") (pinfunction "C_3") (pintype "passive"))
      (node (ref "Q9") (pin "6") (pinfunction "G1_6") (pintype "passive"))
      (node (ref "R3") (pin "2") (pinfunction "2_2") (pintype "passive"))
    )
    (net (code "56") (name "Net-(Q9-D1)") (class "Default")
      (node (ref "Q9") (pin "2") (pinfunction "D1_2") (pintype "passive"))
      (node (ref "Q9") (pin "5") (pinfunction "D2_5") (pintype "passive"))
    )
    (net (code "57") (name "Net-(Q9-G2)") (class "Default")
      (node (ref "C18") (pin "1") (pinfunction "1_1") (pintype "passive"))
      (node (ref "Q9") (pin "4") (pinfunction "G2_4") (pintype "passive"))
      (node (ref "U2") (pin "1") (pinfunction "GATE_1") (pintype "passive"))
    )
    (net (code "58") (name "Net-(Q9-S2)") (class "Default")
      (node (ref "C16") (pin "1") (pinfunction "1_1") (pintype "passive"))
      (node (ref "C17") (pin "1") (pinfunction "1_1") (pintype "passive"))
      (node (ref "C18") (pin "2") (pinfunction "2_2") (pintype "passive"))
      (node (ref "J3") (pin "1") (pinfunction "1_1") (pintype "passive"))
      (node (ref "J3") (pin "10") (pinfunction "10_10") (pintype "passive"))
      (node (ref "J3") (pin "2") (pinfunction "2_2") (pintype "passive"))
      (node (ref "Q9") (pin "3") (pinfunction "S2_3") (pintype "passive"))
      (node (ref "R11") (pin "2") (pinfunction "2_2") (pintype "passive"))
      (node (ref "U2") (pin "2") (pinfunction "GND_2") (pintype "passive"))
      (node (ref "ZD2") (pin "1") (pinfunction "A_1") (pintype "passive"))
    )
    (net (code "59") (name "Net-(Q10-G)") (class "Default")
      (node (ref "Q10") (pin "1") (pinfunction "G_1") (pintype "passive"))
      (node (ref "Q11") (pin "3") (pinfunction "D_3") (pintype "passive"))
      (node (ref "Q12") (pin "1") (pinfunction "G_1") (pintype "passive"))
      (node (ref "R26") (pin "1") (pinfunction "1_1") (pintype "passive"))
    )
    (net (code "60") (name "Net-(Q11-G)") (class "Default")
      (node (ref "Q11") (pin "1") (pinfunction "G_1") (pintype "passive"))
      (node (ref "R23") (pin "2") (pinfunction "2_2") (pintype "passive"))
      (node (ref "R28") (pin "1") (pinfunction "1_1") (pintype "passive"))
    )
    (net (code "61") (name "Net-(Q12-S)") (class "Default")
      (node (ref "Q12") (pin "2") (pinfunction "S_2") (pintype "passive"))
      (node (ref "R17") (pin "2") (pinfunction "2_2") (pintype "passive"))
    )
    (net (code "62") (name "Net-(U1-CS)") (class "Default")
      (node (ref "R2") (pin "2") (pinfunction "2_2") (pintype "passive"))
      (node (ref "U1") (pin "2") (pinfunction "CS_2") (pintype "passive"))
    )
    (net (code "63") (name "Net-(U1-VCC)") (class "Default")
      (node (ref "C1") (pin "2") (pinfunction "2_2") (pintype "passive"))
      (node (ref "R1") (pin "1") (pinfunction "1_1") (pintype "passive"))
      (node (ref "U1") (pin "5") (pinfunction "VCC_5") (pintype "passive"))
    )
    (net (code "64") (name "Net-(U2-VDD)") (class "Default")
      (node (ref "C16") (pin "2") (pinfunction "2_2") (pintype "passive"))
      (node (ref "R11") (pin "1") (pinfunction "1_1") (pintype "passive"))
      (node (ref "R8") (pin "1") (pinfunction "1_1") (pintype "passive"))
      (node (ref "R9") (pin "2") (pinfunction "2_2") (pintype "passive"))
      (node (ref "U2") (pin "5") (pinfunction "VDD_5") (pintype "passive"))
      (node (ref "ZD2") (pin "2") (pinfunction "K_2") (pintype "passive"))
    )
    (net (code "65") (name "Net-(ZD1-A)") (class "Default")
      (node (ref "R4") (pin "1") (pinfunction "1_1") (pintype "passive"))
      (node (ref "ZD1") (pin "1") (pinfunction "A_1") (pintype "passive"))
    )
    (net (code "66") (name "VBUS_B") (class "Default")
      (node (ref "C4") (pin "2") (pinfunction "2_2") (pintype "passive"))
      (node (ref "J1") (pin "1") (pinfunction "VBUS_1") (pintype "passive"))
      (node (ref "J3") (pin "6") (pinfunction "6_6") (pintype "passive"))
      (node (ref "Q5") (pin "1") (pinfunction "S1_1") (pintype "passive"))
      (node (ref "Q5") (pin "3") (pinfunction "S2_3") (pintype "passive"))
      (node (ref "R10") (pin "1") (pinfunction "1_1") (pintype "passive"))
      (node (ref "R3") (pin "1") (pinfunction "1_1") (pintype "passive"))
      (node (ref "R9") (pin "1") (pinfunction "1_1") (pintype "passive"))
      (node (ref "U3") (pin "30") (pinfunction "VBUS_B_30") (pintype "passive"))
      (node (ref "ZD1") (pin "2") (pinfunction "K_2") (pintype "passive"))
    )
    (net (code "67") (name "unconnected-(J3-Pad3)") (class "Default")
      (node (ref "J3") (pin "3") (pinfunction "3_3") (pintype "passive"))
    )
    (net (code "68") (name "unconnected-(J3-Pad4)") (class "Default")
      (node (ref "J3") (pin "4") (pinfunction "4_4") (pintype "passive"))
    )
    (net (code "69") (name "unconnected-(J3-Pad7)") (class "Default")
      (node (ref "J3") (pin "7") (pinfunction "7_7") (pintype "passive"))
    )
    (net (code "70") (name "unconnected-(J3-Pad8)") (class "Default")
      (node (ref "J3") (pin "8") (pinfunction "8_8") (pintype "passive"))
    )
    (net (code "71") (name "unconnected-(J4-SBU1-PadA8)") (class "Default")
      (node (ref "J4") (pin "A8") (pinfunction "SBU1_A8") (pintype "passive"))
    )
    (net (code "72") (name "unconnected-(J4-SBU2-PadB8)") (class "Default")
      (node (ref "J4") (pin "B8") (pinfunction "SBU2_B8") (pintype "passive"))
    )
    (net (code "73") (name "unconnected-(J4-SSRXn1-PadB10)") (class "Default")
      (node (ref "J4") (pin "B10") (pinfunction "SSRXn1_B10") (pintype "passive"))
    )
    (net (code "74") (name "unconnected-(J4-SSRXn2-PadA10)") (class "Default")
      (node (ref "J4") (pin "A10") (pinfunction "SSRXn2_A10") (pintype "passive"))
    )
    (net (code "75") (name "unconnected-(J4-SSRXp1-PadB11)") (class "Default")
      (node (ref "J4") (pin "B11") (pinfunction "SSRXp1_B11") (pintype "passive"))
    )
    (net (code "76") (name "unconnected-(J4-SSRXp2-PadA11)") (class "Default")
      (node (ref "J4") (pin "A11") (pinfunction "SSRXp2_A11") (pintype "passive"))
    )
    (net (code "77") (name "unconnected-(J4-SSTXn1-PadA3)") (class "Default")
      (node (ref "J4") (pin "A3") (pinfunction "SSTXn1_A3") (pintype "passive"))
    )
    (net (code "78") (name "unconnected-(J4-SSTXn2-PadB3)") (class "Default")
      (node (ref "J4") (pin "B3") (pinfunction "SSTXn2_B3") (pintype "passive"))
    )
    (net (code "79") (name "unconnected-(J4-SSTXp1-PadA2)") (class "Default")
      (node (ref "J4") (pin "A2") (pinfunction "SSTXp1_A2") (pintype "passive"))
    )
    (net (code "80") (name "unconnected-(J4-SSTXp2-PadB2)") (class "Default")
      (node (ref "J4") (pin "B2") (pinfunction "SSTXp2_B2") (pintype "passive"))
    )
    (net (code "81") (name "unconnected-(J5-SHIELD1-Pad5)") (class "Default")
      (node (ref "J5") (pin "5") (pinfunction "SHIELD1_5") (pintype "passive"))
    )
    (net (code "82") (name "unconnected-(J5-SHIELD2-Pad6)") (class "Default")
      (node (ref "J5") (pin "6") (pinfunction "SHIELD2_6") (pintype "passive"))
    )
    (net (code "83") (name "unconnected-(Q1-D2-Pad5)") (class "Default")
      (node (ref "Q1") (pin "5") (pinfunction "D2_5") (pintype "passive"))
    )
    (net (code "84") (name "unconnected-(Q4-D1-Pad2)") (class "Default")
      (node (ref "Q4") (pin "2") (pinfunction "D1_2") (pintype "passive"))
    )
    (net (code "85") (name "unconnected-(Q5-D1-Pad2)") (class "Default")
      (node (ref "Q5") (pin "2") (pinfunction "D1_2") (pintype "passive"))
    )
    (net (code "86") (name "unconnected-(Q6-D1-Pad2)") (class "Default")
      (node (ref "Q6") (pin "2") (pinfunction "D1_2") (pintype "passive"))
    )
    (net (code "87") (name "unconnected-(Q8-D1-Pad2)") (class "Default")
      (node (ref "Q8") (pin "2") (pinfunction "D1_2") (pintype "passive"))
    )
    (net (code "88") (name "unconnected-(U1-TD-Pad4)") (class "Default")
      (node (ref "U1") (pin "4") (pinfunction "TD_4") (pintype "passive"))
    )
    (net (code "89") (name "unconnected-(U2-NC1-Pad3)") (class "Default")
      (node (ref "U2") (pin "3") (pinfunction "NC1_3") (pintype "passive"))
    )
    (net (code "90") (name "unconnected-(U2-NC2-Pad4)") (class "Default")
      (node (ref "U2") (pin "4") (pinfunction "NC2_4") (pintype "passive"))
    )
    (net (code "91") (name "unconnected-(U4-PA3-Pad4)") (class "Default")
      (node (ref "U4") (pin "4") (pinfunction "PA3_4") (pintype "passive"))
    )
    (net (code "92") (name "unconnected-(U4-PA7-Pad7)") (class "Default")
      (node (ref "U4") (pin "7") (pinfunction "PA7_7") (pintype "passive"))
    )
    (net (code "93") (name "unconnected-(U4-PB2-Pad6)") (class "Default")
      (node (ref "U4") (pin "6") (pinfunction "PB2_6") (pintype "passive"))
    )
  )
)
